# 24V_Boost.net
KiCad netlist of a schematic drawn in Altium Designer
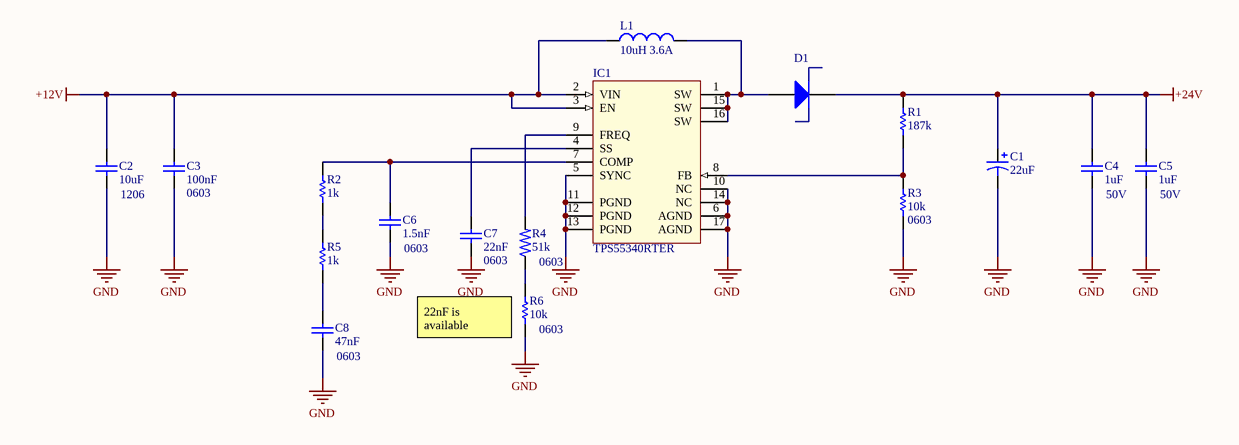
[diagram p0: 24V_Boost.SchDoc]

(export (version "E")
  (design (tool "Eeschema 10.0.6"))
  (components
    (comp (ref "C1")
      (value "22uF")
      (footprint "PCB-jngp9cavmssoy37xiwaz-1")
      (description "Polymer capacitor [Panasonic Automotive & Industrial Systems] 35SVPF22M Polymer capacitor")
      (fields
        (field (name "MANUFACTURE PART NUMBER") "OCV220M1VTR-0606")
        (field (name "MANUFACTURER") "Lelon")
      )
      (libsource (lib "POWER CARD") (part "CMP-ceae0666f79b1169-1"))
    )
    (comp (ref "C2")
      (value "10uF")
      (footprint "CAPC3216X127X50ML20T25")
      (description "CAP CER 0.1UF 100V 10% X7R 1206")
      (fields
        (field (name "MANUFACTURER") "Samsung Electro-Mechanics")
        (field (name "PACKAGE / CASE") "1206")
        (field (name "MANUFACTURE PART NUMBER") "CL31B106KBHNNNE")
      )
      (libsource (lib "POWER CARD") (part "CMP-126371-4"))
    )
    (comp (ref "C3")
      (value "100nF")
      (footprint "CAPC1608X09N")
      (description "0603 10 nF 50 V ± 10% Tolerance X7R Surface Mount Multilayer Ceramic Capacitor")
      (fields
        (field (name "MANUFACTURE PART NUMBER") "CC0603KRX7R9BB104")
        (field (name "MANUFACTURER") "YAGEO")
        (field (name "PACKAGE / CASE") "0603")
      )
      (libsource (lib "POWER CARD") (part "CMP-2f55e5122ad9f092-5"))
    )
    (comp (ref "C4")
      (value "1uF")
      (footprint "CAPC1608X09N")
      (description "0603 10 nF 50 V ± 10% Tolerance X7R Surface Mount Multilayer Ceramic Capacitor")
      (fields
        (field (name "VOLTAGE-RATED") "50V")
        (field (name "MANUFACTURE PART NUMBER") "CL21B105KBFNNNE")
        (field (name "MANUFACTURER") "Samsung Electro-Mechanics")
      )
      (libsource (lib "POWER CARD") (part "CMP-2f55e5122ad9f092-5"))
    )
    (comp (ref "C5")
      (value "1uF")
      (footprint "CAPC1608X09N")
      (description "0603 10 nF 50 V ± 10% Tolerance X7R Surface Mount Multilayer Ceramic Capacitor")
      (fields
        (field (name "VOLTAGE-RATED") "50V")
        (field (name "MANUFACTURE PART NUMBER") "CL21B105KBFNNNE")
        (field (name "MANUFACTURER") "Samsung Electro-Mechanics")
      )
      (libsource (lib "POWER CARD") (part "CMP-2f55e5122ad9f092-5"))
    )
    (comp (ref "C6")
      (value "1.5nF")
      (footprint "CAPC1608X09N")
      (description "0603 10 nF 50 V ± 10% Tolerance X7R Surface Mount Multilayer Ceramic Capacitor")
      (fields
        (field (name "MANUFACTURE PART NUMBER") "0603B152K500CT")
        (field (name "MANUFACTURER") "Walsin Tech Corp")
        (field (name "PACKAGE / CASE") "0603")
      )
      (libsource (lib "POWER CARD") (part "CMP-2f55e5122ad9f092-5"))
    )
    (comp (ref "C7")
      (value "22nF")
      (footprint "CAPC1608X09N")
      (description "0603 10 nF 50 V ± 10% Tolerance X7R Surface Mount Multilayer Ceramic Capacitor")
      (fields
        (field (name "MANUFACTURE PART NUMBER") "CL10B223KB8NNNC")
        (field (name "MANUFACTURER") "Samsung Electro-Mechanics")
        (field (name "PACKAGE / CASE") "0603")
      )
      (libsource (lib "Resistor Capacitor") (part "CMP-2f55e5122ad9f092-5_11"))
    )
    (comp (ref "C8")
      (value "47nF")
      (footprint "CAPC1608X09N")
      (description "0603 10 nF 50 V ± 10% Tolerance X7R Surface Mount Multilayer Ceramic Capacitor")
      (fields
        (field (name "MANUFACTURE PART NUMBER") "0603F473M500CT")
        (field (name "MANUFACTURER") "Walsin Tech Corp")
        (field (name "PACKAGE / CASE") "0603")
      )
      (libsource (lib "POWER CARD") (part "CMP-2f55e5122ad9f092-5"))
    )
    (comp (ref "D1")
      (value "~")
      (footprint "PCB-z3532lqu4iri8rzc55ux-1")
      (description "Diode, Schottky, 5a, 40v, Do-214ab-2, Full Reel")
      (fields
        (field (name "MANUFACTURER") "Diodes Incorporated")
        (field (name "MANUFACTURE PART NUMBER") "B540C-13-F")
      )
      (libsource (lib "POWER CARD") (part "CMP-d6251f2b0bb209e2-2"))
    )
    (comp (ref "IC1")
      (value "TPS55340RTER")
      (footprint "VfQFPN 3x3x1.0 16L")
      (description "Integrated, 5-A 40-V Wide Input Range Boost/SEPIC/Flyback DC-DC Regulator 16-WQFN -40 to 150")
      (fields (field (name "MANUFACTURER") "Texas Instruments"))
      (libsource (lib "POWER CARD") (part "TPS55340RTER"))
    )
    (comp (ref "L1")
      (value "10uH 3.6A")
      (footprint "PCB-aqghgth2fl3irtnr7nhi-1")
      (description "Inductor Power Shielded Wirewound 10uH 20% 100KHz Metal 4.2A 86.35mOhm DCR Automotive T/R")
      (fields (field (name "MANUFACTURE PART NUMBER") "SPM6530T-100M-HZ") (field (name "MANUFACTURER") "TDK"))
      (libsource (lib "POWER CARD") (part "CMP-8deb4183ed4a522c-1"))
    )
    (comp (ref "R1")
      (value "187k")
      (footprint "gen0603-2")
      (description "Surface Mount Thick Film Resistor, RC Series, 1 kohm, 100 mW, - 1%, 50 V, 0603 [1608 Metric]")
      (fields
        (field (name "MANUFACTURER") "UNI-ROYAL(Uniroyal Elec)")
        (field (name "MANUFACTURE PART NUMBER") "0603WAF1873T5E")
      )
      (libsource (lib "POWER CARD") (part "CMP-1853278-27"))
    )
    (comp (ref "R2")
      (value "1k")
      (footprint "gen0603-2")
      (description "Surface Mount Thick Film Resistor, RC Series, 1 kohm, 100 mW, - 1%, 50 V, 0603 [1608 Metric]")
      (fields (field (name "MANUFACTURE PART NUMBER") "RC0603FR-071KL") (field (name "MANUFACTURER") "YAGEO"))
      (libsource (lib "POWER CARD") (part "CMP-1853278-27"))
    )
    (comp (ref "R3")
      (value "10k")
      (footprint "gen0603-2")
      (description "Surface Mount Thick Film Resistor, RC Series, 1 kohm, 100 mW, - 1%, 50 V, 0603 [1608 Metric]")
      (fields
        (field (name "MANUFACTURER") "YAGEO")
        (field (name "MANUFACTURE PART NUMBER") "RC0603FR-0710KL")
        (field (name "PACKAGE / CASE") "0603")
      )
      (libsource (lib "POWER CARD") (part "CMP-1853278-27"))
    )
    (comp (ref "R4")
      (value "51k")
      (footprint "PCB-3elf45qdqizoabmczrxc-1")
      (description "Surface Mount Thick Film Resistor, RC Series, 1 kohm, 100 mW, - 1%, 50 V, 0603 [1608 Metric]")
      (fields
        (field (name "PACKAGE / CASE") "0603")
        (field (name "MANUFACTURER") "Walsin Tech Group")
        (field (name "MANUFACTURE PART NUMBER") "WR06X513 JTL")
      )
      (libsource (lib "POWER CARD") (part "CMP-1853278-23"))
    )
    (comp (ref "R5")
      (value "1k")
      (footprint "gen0603-2")
      (description "Surface Mount Thick Film Resistor, RC Series, 1 kohm, 100 mW, - 1%, 50 V, 0603 [1608 Metric]")
      (fields (field (name "MANUFACTURE PART NUMBER") "RC0603FR-071KL") (field (name "MANUFACTURER") "YAGEO"))
      (libsource (lib "POWER CARD") (part "CMP-1853278-27"))
    )
    (comp (ref "R6")
      (value "10k")
      (footprint "gen0603-2")
      (description "Surface Mount Thick Film Resistor, RC Series, 1 kohm, 100 mW, - 1%, 50 V, 0603 [1608 Metric]")
      (fields
        (field (name "MANUFACTURER") "YAGEO")
        (field (name "MANUFACTURE PART NUMBER") "RC0603FR-0710KL")
        (field (name "PACKAGE / CASE") "0603")
      )
      (libsource (lib "POWER CARD") (part "CMP-1853278-27"))
    )
  )
  (nets
    (net (code "1") (name "+12V") (class "Default")
      (node (ref "C2") (pin "2") (pinfunction "2_2") (pintype "passive"))
      (node (ref "C3") (pin "1") (pinfunction "1_1") (pintype "passive"))
      (node (ref "IC1") (pin "2") (pinfunction "VIN_2") (pintype "input"))
      (node (ref "IC1") (pin "3") (pinfunction "EN_3") (pintype "input"))
      (node (ref "L1") (pin "1") (pinfunction "1_1") (pintype "passive"))
    )
    (net (code "2") (name "+24V") (class "Default")
      (node (ref "C1") (pin "1") (pinfunction "1_1") (pintype "passive"))
      (node (ref "C4") (pin "2") (pinfunction "2_2") (pintype "passive"))
      (node (ref "C5") (pin "2") (pinfunction "2_2") (pintype "passive"))
      (node (ref "D1") (pin "2") (pinfunction "K_2") (pintype "passive"))
      (node (ref "R1") (pin "2") (pinfunction "2_2") (pintype "passive"))
    )
    (net (code "3") (name "GND") (class "Default")
      (node (ref "C1") (pin "2") (pinfunction "2_2") (pintype "passive"))
      (node (ref "C2") (pin "1") (pinfunction "1_1") (pintype "passive"))
      (node (ref "C3") (pin "2") (pinfunction "2_2") (pintype "passive"))
      (node (ref "C4") (pin "1") (pinfunction "1_1") (pintype "passive"))
      (node (ref "C5") (pin "1") (pinfunction "1_1") (pintype "passive"))
      (node (ref "C6") (pin "1") (pinfunction "1_1") (pintype "passive"))
      (node (ref "C7") (pin "1") (pinfunction "1_1") (pintype "passive"))
      (node (ref "C8") (pin "1") (pinfunction "1_1") (pintype "passive"))
      (node (ref "IC1") (pin "10") (pinfunction "NC_10") (pintype "power_in"))
      (node (ref "IC1") (pin "11") (pinfunction "PGND_11") (pintype "power_in"))
      (node (ref "IC1") (pin "12") (pinfunction "PGND_12") (pintype "power_in"))
      (node (ref "IC1") (pin "13") (pinfunction "PGND_13") (pintype "power_in"))
      (node (ref "IC1") (pin "14") (pinfunction "NC_14") (pintype "power_in"))
      (node (ref "IC1") (pin "17") (pinfunction "AGND_17") (pintype "power_in"))
      (node (ref "IC1") (pin "5") (pinfunction "SYNC_5") (pintype "passive"))
      (node (ref "IC1") (pin "6") (pinfunction "AGND_6") (pintype "power_in"))
      (node (ref "R3") (pin "2") (pinfunction "2_2") (pintype "passive"))
      (node (ref "R6") (pin "1") (pinfunction "1_1") (pintype "passive"))
    )
    (net (code "4") (name "Net-(C8-Pad2)") (class "Default")
      (node (ref "C8") (pin "2") (pinfunction "2_2") (pintype "passive"))
      (node (ref "R5") (pin "2") (pinfunction "2_2") (pintype "passive"))
    )
    (net (code "5") (name "Net-(D1-A)") (class "Default")
      (node (ref "D1") (pin "1") (pinfunction "A_1") (pintype "passive"))
      (node (ref "IC1") (pin "1") (pinfunction "SW_1") (pintype "passive"))
      (node (ref "IC1") (pin "15") (pinfunction "SW_15") (pintype "passive"))
      (node (ref "IC1") (pin "16") (pinfunction "SW_16") (pintype "passive"))
      (node (ref "L1") (pin "2") (pinfunction "2_2") (pintype "passive"))
    )
    (net (code "6") (name "Net-(IC1-COMP)") (class "Default")
      (node (ref "C6") (pin "2") (pinfunction "2_2") (pintype "passive"))
      (node (ref "IC1") (pin "7") (pinfunction "COMP_7") (pintype "passive"))
      (node (ref "R2") (pin "2") (pinfunction "2_2") (pintype "passive"))
    )
    (net (code "7") (name "Net-(IC1-FB)") (class "Default")
      (node (ref "IC1") (pin "8") (pinfunction "FB_8") (pintype "input"))
      (node (ref "R1") (pin "1") (pinfunction "1_1") (pintype "passive"))
      (node (ref "R3") (pin "1") (pinfunction "1_1") (pintype "passive"))
    )
    (net (code "8") (name "Net-(IC1-FREQ)") (class "Default")
      (node (ref "IC1") (pin "9") (pinfunction "FREQ_9") (pintype "passive"))
      (node (ref "R4") (pin "2") (pinfunction "2_2") (pintype "passive"))
    )
    (net (code "9") (name "Net-(IC1-SS)") (class "Default")
      (node (ref "C7") (pin "2") (pinfunction "2_2") (pintype "passive"))
      (node (ref "IC1") (pin "4") (pinfunction "SS_4") (pintype "passive"))
    )
    (net (code "10") (name "Net-(R2-Pad1)") (class "Default")
      (node (ref "R2") (pin "1") (pinfunction "1_1") (pintype "passive"))
      (node (ref "R5") (pin "1") (pinfunction "1_1") (pintype "passive"))
    )
    (net (code "11") (name "Net-(R4-Pad1)") (class "Default")
      (node (ref "R4") (pin "1") (pinfunction "1_1") (pintype "passive"))
      (node (ref "R6") (pin "2") (pinfunction "2_2") (pintype "passive"))
    )
  )
)
